# Microcontroller.net
KiCad netlist of a schematic drawn in Altium Designer
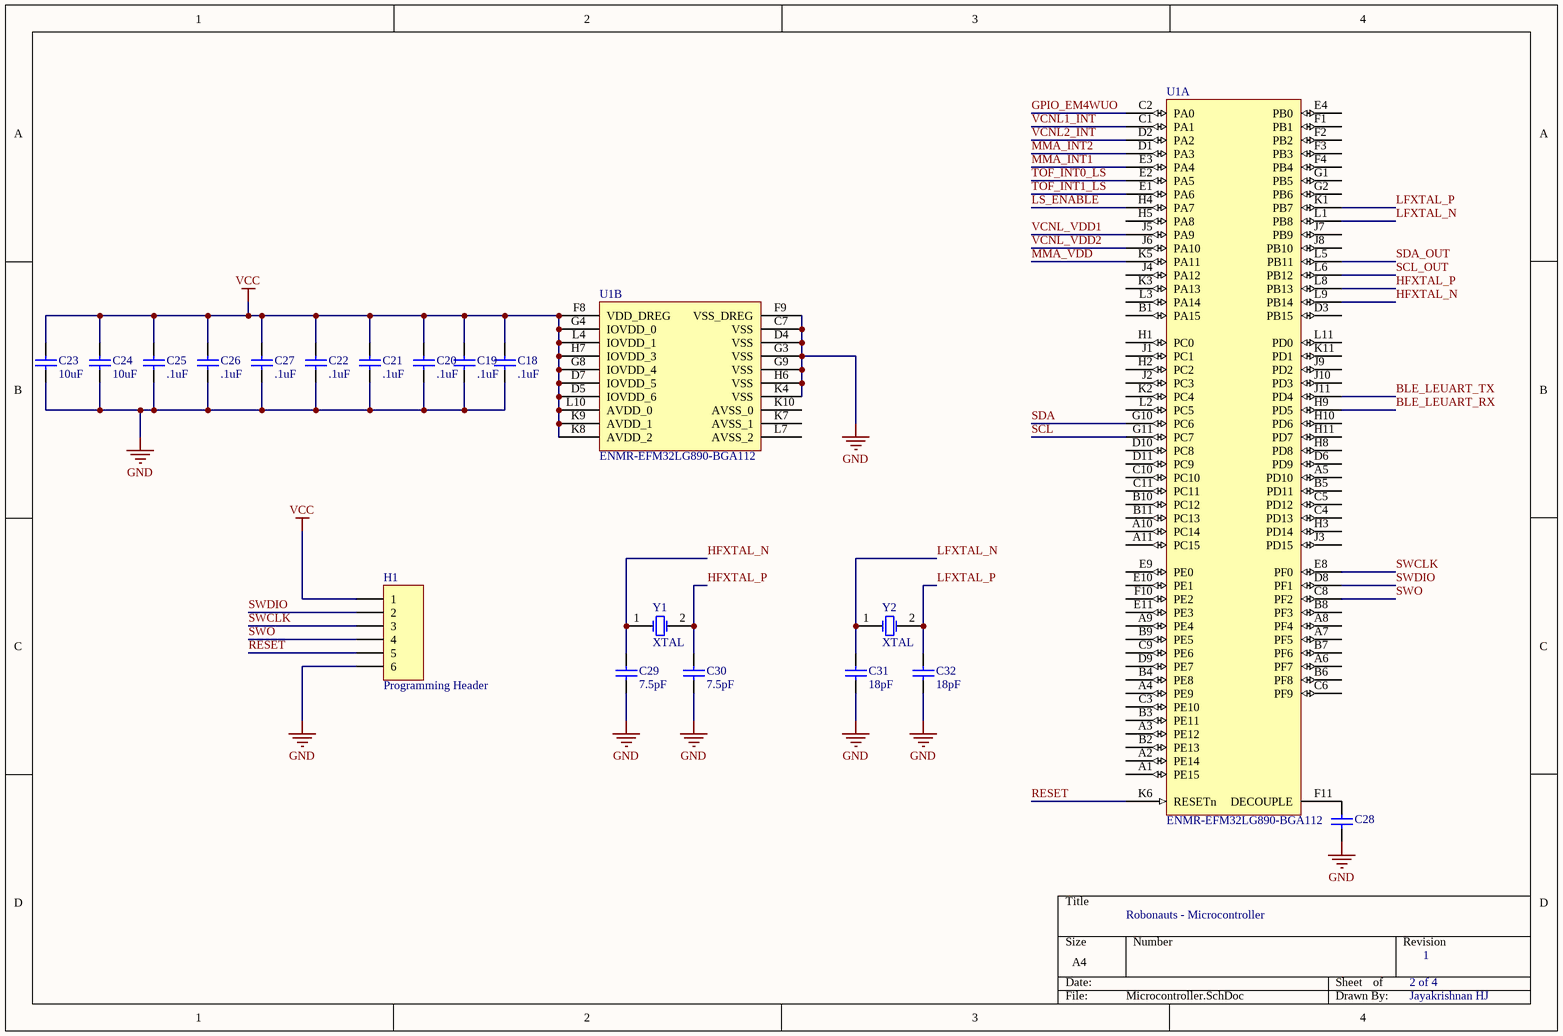
[diagram p0: Microcontroller.SchDoc]

(export (version "E")
  (design (tool "Eeschema 10.0.6"))
  (components
    (comp (ref "C18")
      (value ".1uF")
      (footprint "1608[0603]")
      (description "Capacitor (Semiconductor SIM Model)")
      (fields (field (name "Comment") "Cap Semi") (field (name "PUBLISHER") "Altium Limited"))
      (libsource (lib "Miscellaneous Devices") (part "Cap Semi"))
    )
    (comp (ref "C19")
      (value ".1uF")
      (footprint "1608[0603]")
      (description "Capacitor (Semiconductor SIM Model)")
      (fields (field (name "Comment") "Cap Semi") (field (name "PUBLISHER") "Altium Limited"))
      (libsource (lib "Miscellaneous Devices") (part "Cap Semi"))
    )
    (comp (ref "C20")
      (value ".1uF")
      (footprint "1608[0603]")
      (description "Capacitor (Semiconductor SIM Model)")
      (fields (field (name "Comment") "Cap Semi") (field (name "PUBLISHER") "Altium Limited"))
      (libsource (lib "Miscellaneous Devices") (part "Cap Semi"))
    )
    (comp (ref "C21")
      (value ".1uF")
      (footprint "1608[0603]")
      (description "Capacitor (Semiconductor SIM Model)")
      (fields (field (name "Comment") "Cap Semi") (field (name "PUBLISHER") "Altium Limited"))
      (libsource (lib "Miscellaneous Devices") (part "Cap Semi"))
    )
    (comp (ref "C22")
      (value ".1uF")
      (footprint "1608[0603]")
      (description "Capacitor (Semiconductor SIM Model)")
      (fields (field (name "Comment") "Cap Semi") (field (name "PUBLISHER") "Altium Limited"))
      (libsource (lib "Miscellaneous Devices") (part "Cap Semi"))
    )
    (comp (ref "C23")
      (value "10uF")
      (footprint "1608[0603]")
      (description "Capacitor (Semiconductor SIM Model)")
      (fields (field (name "Comment") "Cap Semi") (field (name "PUBLISHER") "Altium Limited"))
      (libsource (lib "Miscellaneous Devices") (part "Cap Semi"))
    )
    (comp (ref "C24")
      (value "10uF")
      (footprint "1608[0603]")
      (description "Capacitor (Semiconductor SIM Model)")
      (fields (field (name "Comment") "Cap Semi") (field (name "PUBLISHER") "Altium Limited"))
      (libsource (lib "Miscellaneous Devices") (part "Cap Semi"))
    )
    (comp (ref "C25")
      (value ".1uF")
      (footprint "1608[0603]")
      (description "Capacitor (Semiconductor SIM Model)")
      (fields (field (name "Comment") "Cap Semi") (field (name "PUBLISHER") "Altium Limited"))
      (libsource (lib "Miscellaneous Devices") (part "Cap Semi"))
    )
    (comp (ref "C26")
      (value ".1uF")
      (footprint "1608[0603]")
      (description "Capacitor (Semiconductor SIM Model)")
      (fields (field (name "Comment") "Cap Semi") (field (name "PUBLISHER") "Altium Limited"))
      (libsource (lib "Miscellaneous Devices") (part "Cap Semi"))
    )
    (comp (ref "C27")
      (value ".1uF")
      (footprint "1608[0603]")
      (description "Capacitor (Semiconductor SIM Model)")
      (fields (field (name "Comment") "Cap Semi") (field (name "PUBLISHER") "Altium Limited"))
      (libsource (lib "Miscellaneous Devices") (part "Cap Semi"))
    )
    (comp (ref "C28")
      (value "Cap Semi")
      (footprint "1608[0603]")
      (description "Capacitor (Semiconductor SIM Model)")
      (fields (field (name "PUBLISHER") "Altium Limited"))
      (libsource (lib "Miscellaneous Devices") (part "Cap Semi"))
    )
    (comp (ref "C29")
      (value "7.5pF")
      (footprint "C1206")
      (description "Capacitor (Semiconductor SIM Model)")
      (fields (field (name "Comment") "Cap Semi") (field (name "PUBLISHER") "Altium Limited"))
      (libsource (lib "Miscellaneous Devices") (part "Cap Semi"))
    )
    (comp (ref "C30")
      (value "7.5pF")
      (footprint "C1206")
      (description "Capacitor (Semiconductor SIM Model)")
      (fields (field (name "Comment") "Cap Semi") (field (name "PUBLISHER") "Altium Limited"))
      (libsource (lib "Miscellaneous Devices") (part "Cap Semi"))
    )
    (comp (ref "C31")
      (value "18pF")
      (footprint "C1206")
      (description "Capacitor (Semiconductor SIM Model)")
      (fields (field (name "Comment") "Cap Semi") (field (name "PUBLISHER") "Altium Limited"))
      (libsource (lib "Miscellaneous Devices") (part "Cap Semi"))
    )
    (comp (ref "C32")
      (value "18pF")
      (footprint "C1206")
      (description "Capacitor (Semiconductor SIM Model)")
      (fields (field (name "Comment") "Cap Semi") (field (name "PUBLISHER") "Altium Limited"))
      (libsource (lib "Miscellaneous Devices") (part "Cap Semi"))
    )
    (comp (ref "H1")
      (value "Programming Header")
      (footprint "HDR1X6")
      (description "Header, 6-Pin")
      (fields (field (name "PUBLISHER") "Altium Limited"))
      (libsource (lib "Miscellaneous Connectors") (part "Header 6"))
    )
    (comp (ref "U1")
      (value "ENMR-EFM32LG890-BGA112")
      (footprint "ENMR-BGA112")
      (libsource (lib "Robonauts_parts") (part "ENMR-EFM32LG890-BGA112"))
    )
    (comp (ref "Y1")
      (value "XTAL")
      (footprint "R38")
      (description "Crystal Oscillator")
      (fields (field (name "PUBLISHER") "Altium Limited"))
      (libsource (lib "Miscellaneous Devices") (part "XTAL"))
    )
    (comp (ref "Y2")
      (value "XTAL")
      (footprint "R38")
      (description "Crystal Oscillator")
      (fields (field (name "PUBLISHER") "Altium Limited"))
      (libsource (lib "Miscellaneous Devices") (part "XTAL"))
    )
  )
  (nets
    (net (code "1") (name "/BLE_LEUART_RX") (class "Default")
      (node (ref "U1") (pin "H9") (pinfunction "PD5_H9") (pintype "bidirectional"))
    )
    (net (code "2") (name "/BLE_LEUART_TX") (class "Default")
      (node (ref "U1") (pin "J11") (pinfunction "PD4_J11") (pintype "bidirectional"))
    )
    (net (code "3") (name "/GPIO_EM4WUO") (class "Default")
      (node (ref "U1") (pin "C2") (pinfunction "PA0_C2") (pintype "bidirectional"))
    )
    (net (code "4") (name "/HFXTAL_N") (class "Default")
      (node (ref "C29") (pin "2") (pinfunction "2_2") (pintype "passive"))
      (node (ref "U1") (pin "L9") (pinfunction "PB14_L9") (pintype "bidirectional"))
      (node (ref "Y1") (pin "1") (pinfunction "OSC1_1") (pintype "passive"))
    )
    (net (code "5") (name "/HFXTAL_P") (class "Default")
      (node (ref "C30") (pin "2") (pinfunction "2_2") (pintype "passive"))
      (node (ref "U1") (pin "L8") (pinfunction "PB13_L8") (pintype "bidirectional"))
      (node (ref "Y1") (pin "2") (pinfunction "OSC2_2") (pintype "passive"))
    )
    (net (code "6") (name "/LFXTAL_N") (class "Default")
      (node (ref "C31") (pin "2") (pinfunction "2_2") (pintype "passive"))
      (node (ref "U1") (pin "L1") (pinfunction "PB8_L1") (pintype "bidirectional"))
      (node (ref "Y2") (pin "1") (pinfunction "OSC1_1") (pintype "passive"))
    )
    (net (code "7") (name "/LFXTAL_P") (class "Default")
      (node (ref "C32") (pin "2") (pinfunction "2_2") (pintype "passive"))
      (node (ref "U1") (pin "K1") (pinfunction "PB7_K1") (pintype "bidirectional"))
      (node (ref "Y2") (pin "2") (pinfunction "OSC2_2") (pintype "passive"))
    )
    (net (code "8") (name "/LS_ENABLE") (class "Default")
      (node (ref "U1") (pin "H4") (pinfunction "PA7_H4") (pintype "bidirectional"))
    )
    (net (code "9") (name "/MMA_INT1") (class "Default")
      (node (ref "U1") (pin "E3") (pinfunction "PA4_E3") (pintype "bidirectional"))
    )
    (net (code "10") (name "/MMA_INT2") (class "Default")
      (node (ref "U1") (pin "D1") (pinfunction "PA3_D1") (pintype "bidirectional"))
    )
    (net (code "11") (name "/MMA_VDD") (class "Default")
      (node (ref "U1") (pin "K5") (pinfunction "PA11_K5") (pintype "bidirectional"))
    )
    (net (code "12") (name "/RESET") (class "Default")
      (node (ref "H1") (pin "5") (pinfunction "5_5") (pintype "passive"))
      (node (ref "U1") (pin "K6") (pinfunction "RESETn_K6") (pintype "input"))
    )
    (net (code "13") (name "/SCL") (class "Default")
      (node (ref "U1") (pin "G11") (pinfunction "PC7_G11") (pintype "bidirectional"))
    )
    (net (code "14") (name "/SCL_OUT") (class "Default")
      (node (ref "U1") (pin "L6") (pinfunction "PB12_L6") (pintype "bidirectional"))
    )
    (net (code "15") (name "/SDA") (class "Default")
      (node (ref "U1") (pin "G10") (pinfunction "PC6_G10") (pintype "bidirectional"))
    )
    (net (code "16") (name "/SDA_OUT") (class "Default")
      (node (ref "U1") (pin "L5") (pinfunction "PB11_L5") (pintype "bidirectional"))
    )
    (net (code "17") (name "/SWCLK") (class "Default")
      (node (ref "H1") (pin "3") (pinfunction "3_3") (pintype "passive"))
      (node (ref "U1") (pin "E8") (pinfunction "PF0_E8") (pintype "bidirectional"))
    )
    (net (code "18") (name "/SWDIO") (class "Default")
      (node (ref "H1") (pin "2") (pinfunction "2_2") (pintype "passive"))
      (node (ref "U1") (pin "D8") (pinfunction "PF1_D8") (pintype "bidirectional"))
    )
    (net (code "19") (name "/SWO") (class "Default")
      (node (ref "H1") (pin "4") (pinfunction "4_4") (pintype "passive"))
      (node (ref "U1") (pin "C8") (pinfunction "PF2_C8") (pintype "bidirectional"))
    )
    (net (code "20") (name "/TOF_INT0_LS") (class "Default")
      (node (ref "U1") (pin "E2") (pinfunction "PA5_E2") (pintype "bidirectional"))
    )
    (net (code "21") (name "/TOF_INT1_LS") (class "Default")
      (node (ref "U1") (pin "E1") (pinfunction "PA6_E1") (pintype "bidirectional"))
    )
    (net (code "22") (name "/VCNL1_INT") (class "Default")
      (node (ref "U1") (pin "C1") (pinfunction "PA1_C1") (pintype "bidirectional"))
    )
    (net (code "23") (name "/VCNL2_INT") (class "Default")
      (node (ref "U1") (pin "D2") (pinfunction "PA2_D2") (pintype "bidirectional"))
    )
    (net (code "24") (name "/VCNL_VDD1") (class "Default")
      (node (ref "U1") (pin "J5") (pinfunction "PA9_J5") (pintype "bidirectional"))
    )
    (net (code "25") (name "/VCNL_VDD2") (class "Default")
      (node (ref "U1") (pin "J6") (pinfunction "PA10_J6") (pintype "bidirectional"))
    )
    (net (code "26") (name "GND") (class "Default")
      (node (ref "C18") (pin "1") (pinfunction "1_1") (pintype "passive"))
      (node (ref "C19") (pin "1") (pinfunction "1_1") (pintype "passive"))
      (node (ref "C20") (pin "1") (pinfunction "1_1") (pintype "passive"))
      (node (ref "C21") (pin "1") (pinfunction "1_1") (pintype "passive"))
      (node (ref "C22") (pin "1") (pinfunction "1_1") (pintype "passive"))
      (node (ref "C23") (pin "1") (pinfunction "1_1") (pintype "passive"))
      (node (ref "C24") (pin "1") (pinfunction "1_1") (pintype "passive"))
      (node (ref "C25") (pin "1") (pinfunction "1_1") (pintype "passive"))
      (node (ref "C26") (pin "1") (pinfunction "1_1") (pintype "passive"))
      (node (ref "C27") (pin "1") (pinfunction "1_1") (pintype "passive"))
      (node (ref "C28") (pin "1") (pinfunction "1_1") (pintype "passive"))
      (node (ref "C29") (pin "1") (pinfunction "1_1") (pintype "passive"))
      (node (ref "C30") (pin "1") (pinfunction "1_1") (pintype "passive"))
      (node (ref "C31") (pin "1") (pinfunction "1_1") (pintype "passive"))
      (node (ref "C32") (pin "1") (pinfunction "1_1") (pintype "passive"))
      (node (ref "H1") (pin "6") (pinfunction "6_6") (pintype "passive"))
      (node (ref "U1") (pin "C7") (pinfunction "VSS_C7") (pintype "power_in"))
      (node (ref "U1") (pin "D4") (pinfunction "VSS_D4") (pintype "power_in"))
      (node (ref "U1") (pin "F9") (pinfunction "VSS_DREG_F9") (pintype "power_in"))
      (node (ref "U1") (pin "G3") (pinfunction "VSS_G3") (pintype "power_in"))
      (node (ref "U1") (pin "G9") (pinfunction "VSS_G9") (pintype "power_in"))
      (node (ref "U1") (pin "H6") (pinfunction "VSS_H6") (pintype "power_in"))
      (node (ref "U1") (pin "K4") (pinfunction "VSS_K4") (pintype "power_in"))
    )
    (net (code "27") (name "Net-(U1A-DECOUPLE)") (class "Default")
      (node (ref "C28") (pin "2") (pinfunction "2_2") (pintype "passive"))
      (node (ref "U1") (pin "F11") (pinfunction "DECOUPLE_F11") (pintype "passive"))
    )
    (net (code "28") (name "VCC") (class "Default")
      (node (ref "C18") (pin "2") (pinfunction "2_2") (pintype "passive"))
      (node (ref "C19") (pin "2") (pinfunction "2_2") (pintype "passive"))
      (node (ref "C20") (pin "2") (pinfunction "2_2") (pintype "passive"))
      (node (ref "C21") (pin "2") (pinfunction "2_2") (pintype "passive"))
      (node (ref "C22") (pin "2") (pinfunction "2_2") (pintype "passive"))
      (node (ref "C23") (pin "2") (pinfunction "2_2") (pintype "passive"))
      (node (ref "C24") (pin "2") (pinfunction "2_2") (pintype "passive"))
      (node (ref "C25") (pin "2") (pinfunction "2_2") (pintype "passive"))
      (node (ref "C26") (pin "2") (pinfunction "2_2") (pintype "passive"))
      (node (ref "C27") (pin "2") (pinfunction "2_2") (pintype "passive"))
      (node (ref "H1") (pin "1") (pinfunction "1_1") (pintype "passive"))
      (node (ref "U1") (pin "D5") (pinfunction "IOVDD_6_D5") (pintype "power_in"))
      (node (ref "U1") (pin "D7") (pinfunction "IOVDD_5_D7") (pintype "power_in"))
      (node (ref "U1") (pin "F8") (pinfunction "VDD_DREG_F8") (pintype "power_in"))
      (node (ref "U1") (pin "G4") (pinfunction "IOVDD_0_G4") (pintype "power_in"))
      (node (ref "U1") (pin "G8") (pinfunction "IOVDD_4_G8") (pintype "power_in"))
      (node (ref "U1") (pin "H7") (pinfunction "IOVDD_3_H7") (pintype "power_in"))
      (node (ref "U1") (pin "K8") (pinfunction "AVDD_2_K8") (pintype "power_in"))
      (node (ref "U1") (pin "K9") (pinfunction "AVDD_1_K9") (pintype "power_in"))
      (node (ref "U1") (pin "L10") (pinfunction "AVDD_0_L10") (pintype "power_in"))
      (node (ref "U1") (pin "L4") (pinfunction "IOVDD_1_L4") (pintype "power_in"))
    )
    (net (code "29") (name "unconnected-(U1A-PA8-PadH5)") (class "Default")
      (node (ref "U1") (pin "H5") (pinfunction "PA8_H5") (pintype "bidirectional"))
    )
    (net (code "30") (name "unconnected-(U1A-PA12-PadJ4)") (class "Default")
      (node (ref "U1") (pin "J4") (pinfunction "PA12_J4") (pintype "bidirectional"))
    )
    (net (code "31") (name "unconnected-(U1A-PA13-PadK3)") (class "Default")
      (node (ref "U1") (pin "K3") (pinfunction "PA13_K3") (pintype "bidirectional"))
    )
    (net (code "32") (name "unconnected-(U1A-PA14-PadL3)") (class "Default")
      (node (ref "U1") (pin "L3") (pinfunction "PA14_L3") (pintype "bidirectional"))
    )
    (net (code "33") (name "unconnected-(U1A-PA15-PadB1)") (class "Default")
      (node (ref "U1") (pin "B1") (pinfunction "PA15_B1") (pintype "bidirectional"))
    )
    (net (code "34") (name "unconnected-(U1A-PB0-PadE4)") (class "Default")
      (node (ref "U1") (pin "E4") (pinfunction "PB0_E4") (pintype "bidirectional"))
    )
    (net (code "35") (name "unconnected-(U1A-PB1-PadF1)") (class "Default")
      (node (ref "U1") (pin "F1") (pinfunction "PB1_F1") (pintype "bidirectional"))
    )
    (net (code "36") (name "unconnected-(U1A-PB2-PadF2)") (class "Default")
      (node (ref "U1") (pin "F2") (pinfunction "PB2_F2") (pintype "bidirectional"))
    )
    (net (code "37") (name "unconnected-(U1A-PB3-PadF3)") (class "Default")
      (node (ref "U1") (pin "F3") (pinfunction "PB3_F3") (pintype "bidirectional"))
    )
    (net (code "38") (name "unconnected-(U1A-PB4-PadF4)") (class "Default")
      (node (ref "U1") (pin "F4") (pinfunction "PB4_F4") (pintype "bidirectional"))
    )
    (net (code "39") (name "unconnected-(U1A-PB5-PadG1)") (class "Default")
      (node (ref "U1") (pin "G1") (pinfunction "PB5_G1") (pintype "bidirectional"))
    )
    (net (code "40") (name "unconnected-(U1A-PB6-PadG2)") (class "Default")
      (node (ref "U1") (pin "G2") (pinfunction "PB6_G2") (pintype "bidirectional"))
    )
    (net (code "41") (name "unconnected-(U1A-PB9-PadJ7)") (class "Default")
      (node (ref "U1") (pin "J7") (pinfunction "PB9_J7") (pintype "bidirectional"))
    )
    (net (code "42") (name "unconnected-(U1A-PB10-PadJ8)") (class "Default")
      (node (ref "U1") (pin "J8") (pinfunction "PB10_J8") (pintype "bidirectional"))
    )
    (net (code "43") (name "unconnected-(U1A-PB15-PadD3)") (class "Default")
      (node (ref "U1") (pin "D3") (pinfunction "PB15_D3") (pintype "bidirectional"))
    )
    (net (code "44") (name "unconnected-(U1A-PC0-PadH1)") (class "Default")
      (node (ref "U1") (pin "H1") (pinfunction "PC0_H1") (pintype "bidirectional"))
    )
    (net (code "45") (name "unconnected-(U1A-PC1-PadJ1)") (class "Default")
      (node (ref "U1") (pin "J1") (pinfunction "PC1_J1") (pintype "bidirectional"))
    )
    (net (code "46") (name "unconnected-(U1A-PC2-PadH2)") (class "Default")
      (node (ref "U1") (pin "H2") (pinfunction "PC2_H2") (pintype "bidirectional"))
    )
    (net (code "47") (name "unconnected-(U1A-PC3-PadJ2)") (class "Default")
      (node (ref "U1") (pin "J2") (pinfunction "PC3_J2") (pintype "bidirectional"))
    )
    (net (code "48") (name "unconnected-(U1A-PC4-PadK2)") (class "Default")
      (node (ref "U1") (pin "K2") (pinfunction "PC4_K2") (pintype "bidirectional"))
    )
    (net (code "49") (name "unconnected-(U1A-PC5-PadL2)") (class "Default")
      (node (ref "U1") (pin "L2") (pinfunction "PC5_L2") (pintype "bidirectional"))
    )
    (net (code "50") (name "unconnected-(U1A-PC8-PadD10)") (class "Default")
      (node (ref "U1") (pin "D10") (pinfunction "PC8_D10") (pintype "bidirectional"))
    )
    (net (code "51") (name "unconnected-(U1A-PC9-PadD11)") (class "Default")
      (node (ref "U1") (pin "D11") (pinfunction "PC9_D11") (pintype "bidirectional"))
    )
    (net (code "52") (name "unconnected-(U1A-PC10-PadC10)") (class "Default")
      (node (ref "U1") (pin "C10") (pinfunction "PC10_C10") (pintype "bidirectional"))
    )
    (net (code "53") (name "unconnected-(U1A-PC11-PadC11)") (class "Default")
      (node (ref "U1") (pin "C11") (pinfunction "PC11_C11") (pintype "bidirectional"))
    )
    (net (code "54") (name "unconnected-(U1A-PC12-PadB10)") (class "Default")
      (node (ref "U1") (pin "B10") (pinfunction "PC12_B10") (pintype "bidirectional"))
    )
    (net (code "55") (name "unconnected-(U1A-PC13-PadB11)") (class "Default")
      (node (ref "U1") (pin "B11") (pinfunction "PC13_B11") (pintype "bidirectional"))
    )
    (net (code "56") (name "unconnected-(U1A-PC14-PadA10)") (class "Default")
      (node (ref "U1") (pin "A10") (pinfunction "PC14_A10") (pintype "bidirectional"))
    )
    (net (code "57") (name "unconnected-(U1A-PC15-PadA11)") (class "Default")
      (node (ref "U1") (pin "A11") (pinfunction "PC15_A11") (pintype "bidirectional"))
    )
    (net (code "58") (name "unconnected-(U1A-PD0-PadL11)") (class "Default")
      (node (ref "U1") (pin "L11") (pinfunction "PD0_L11") (pintype "bidirectional"))
    )
    (net (code "59") (name "unconnected-(U1A-PD1-PadK11)") (class "Default")
      (node (ref "U1") (pin "K11") (pinfunction "PD1_K11") (pintype "bidirectional"))
    )
    (net (code "60") (name "unconnected-(U1A-PD2-PadJ9)") (class "Default")
      (node (ref "U1") (pin "J9") (pinfunction "PD2_J9") (pintype "bidirectional"))
    )
    (net (code "61") (name "unconnected-(U1A-PD3-PadJ10)") (class "Default")
      (node (ref "U1") (pin "J10") (pinfunction "PD3_J10") (pintype "bidirectional"))
    )
    (net (code "62") (name "unconnected-(U1A-PD6-PadH10)") (class "Default")
      (node (ref "U1") (pin "H10") (pinfunction "PD6_H10") (pintype "bidirectional"))
    )
    (net (code "63") (name "unconnected-(U1A-PD7-PadH11)") (class "Default")
      (node (ref "U1") (pin "H11") (pinfunction "PD7_H11") (pintype "bidirectional"))
    )
    (net (code "64") (name "unconnected-(U1A-PD8-PadH8)") (class "Default")
      (node (ref "U1") (pin "H8") (pinfunction "PD8_H8") (pintype "bidirectional"))
    )
    (net (code "65") (name "unconnected-(U1A-PD9-PadD6)") (class "Default")
      (node (ref "U1") (pin "D6") (pinfunction "PD9_D6") (pintype "bidirectional"))
    )
    (net (code "66") (name "unconnected-(U1A-PD10-PadA5)") (class "Default")
      (node (ref "U1") (pin "A5") (pinfunction "PD10_A5") (pintype "bidirectional"))
    )
    (net (code "67") (name "unconnected-(U1A-PD11-PadB5)") (class "Default")
      (node (ref "U1") (pin "B5") (pinfunction "PD11_B5") (pintype "bidirectional"))
    )
    (net (code "68") (name "unconnected-(U1A-PD12-PadC5)") (class "Default")
      (node (ref "U1") (pin "C5") (pinfunction "PD12_C5") (pintype "bidirectional"))
    )
    (net (code "69") (name "unconnected-(U1A-PD13-PadC4)") (class "Default")
      (node (ref "U1") (pin "C4") (pinfunction "PD13_C4") (pintype "bidirectional"))
    )
    (net (code "70") (name "unconnected-(U1A-PD14-PadH3)") (class "Default")
      (node (ref "U1") (pin "H3") (pinfunction "PD14_H3") (pintype "bidirectional"))
    )
    (net (code "71") (name "unconnected-(U1A-PD15-PadJ3)") (class "Default")
      (node (ref "U1") (pin "J3") (pinfunction "PD15_J3") (pintype "bidirectional"))
    )
    (net (code "72") (name "unconnected-(U1A-PE0-PadE9)") (class "Default")
      (node (ref "U1") (pin "E9") (pinfunction "PE0_E9") (pintype "bidirectional"))
    )
    (net (code "73") (name "unconnected-(U1A-PE1-PadE10)") (class "Default")
      (node (ref "U1") (pin "E10") (pinfunction "PE1_E10") (pintype "bidirectional"))
    )
    (net (code "74") (name "unconnected-(U1A-PE2-PadF10)") (class "Default")
      (node (ref "U1") (pin "F10") (pinfunction "PE2_F10") (pintype "bidirectional"))
    )
    (net (code "75") (name "unconnected-(U1A-PE3-PadE11)") (class "Default")
      (node (ref "U1") (pin "E11") (pinfunction "PE3_E11") (pintype "bidirectional"))
    )
    (net (code "76") (name "unconnected-(U1A-PE4-PadA9)") (class "Default")
      (node (ref "U1") (pin "A9") (pinfunction "PE4_A9") (pintype "bidirectional"))
    )
    (net (code "77") (name "unconnected-(U1A-PE5-PadB9)") (class "Default")
      (node (ref "U1") (pin "B9") (pinfunction "PE5_B9") (pintype "bidirectional"))
    )
    (net (code "78") (name "unconnected-(U1A-PE6-PadC9)") (class "Default")
      (node (ref "U1") (pin "C9") (pinfunction "PE6_C9") (pintype "bidirectional"))
    )
    (net (code "79") (name "unconnected-(U1A-PE7-PadD9)") (class "Default")
      (node (ref "U1") (pin "D9") (pinfunction "PE7_D9") (pintype "bidirectional"))
    )
    (net (code "80") (name "unconnected-(U1A-PE8-PadB4)") (class "Default")
      (node (ref "U1") (pin "B4") (pinfunction "PE8_B4") (pintype "bidirectional"))
    )
    (net (code "81") (name "unconnected-(U1A-PE9-PadA4)") (class "Default")
      (node (ref "U1") (pin "A4") (pinfunction "PE9_A4") (pintype "bidirectional"))
    )
    (net (code "82") (name "unconnected-(U1A-PE10-PadC3)") (class "Default")
      (node (ref "U1") (pin "C3") (pinfunction "PE10_C3") (pintype "bidirectional"))
    )
    (net (code "83") (name "unconnected-(U1A-PE11-PadB3)") (class "Default")
      (node (ref "U1") (pin "B3") (pinfunction "PE11_B3") (pintype "bidirectional"))
    )
    (net (code "84") (name "unconnected-(U1A-PE12-PadA3)") (class "Default")
      (node (ref "U1") (pin "A3") (pinfunction "PE12_A3") (pintype "bidirectional"))
    )
    (net (code "85") (name "unconnected-(U1A-PE13-PadB2)") (class "Default")
      (node (ref "U1") (pin "B2") (pinfunction "PE13_B2") (pintype "bidirectional"))
    )
    (net (code "86") (name "unconnected-(U1A-PE14-PadA2)") (class "Default")
      (node (ref "U1") (pin "A2") (pinfunction "PE14_A2") (pintype "bidirectional"))
    )
    (net (code "87") (name "unconnected-(U1A-PE15-PadA1)") (class "Default")
      (node (ref "U1") (pin "A1") (pinfunction "PE15_A1") (pintype "bidirectional"))
    )
    (net (code "88") (name "unconnected-(U1A-PF3-PadB8)") (class "Default")
      (node (ref "U1") (pin "B8") (pinfunction "PF3_B8") (pintype "bidirectional"))
    )
    (net (code "89") (name "unconnected-(U1A-PF4-PadA8)") (class "Default")
      (node (ref "U1") (pin "A8") (pinfunction "PF4_A8") (pintype "bidirectional"))
    )
    (net (code "90") (name "unconnected-(U1A-PF5-PadA7)") (class "Default")
      (node (ref "U1") (pin "A7") (pinfunction "PF5_A7") (pintype "bidirectional"))
    )
    (net (code "91") (name "unconnected-(U1A-PF6-PadB7)") (class "Default")
      (node (ref "U1") (pin "B7") (pinfunction "PF6_B7") (pintype "bidirectional"))
    )
    (net (code "92") (name "unconnected-(U1A-PF7-PadA6)") (class "Default")
      (node (ref "U1") (pin "A6") (pinfunction "PF7_A6") (pintype "bidirectional"))
    )
    (net (code "93") (name "unconnected-(U1A-PF8-PadB6)") (class "Default")
      (node (ref "U1") (pin "B6") (pinfunction "PF8_B6") (pintype "bidirectional"))
    )
    (net (code "94") (name "unconnected-(U1A-PF9-PadC6)") (class "Default")
      (node (ref "U1") (pin "C6") (pinfunction "PF9_C6") (pintype "bidirectional"))
    )
    (net (code "95") (name "unconnected-(U1B-AVSS_0-PadK10)") (class "Default")
      (node (ref "U1") (pin "K10") (pinfunction "AVSS_0_K10") (pintype "power_in"))
    )
    (net (code "96") (name "unconnected-(U1B-AVSS_1-PadK7)") (class "Default")
      (node (ref "U1") (pin "K7") (pinfunction "AVSS_1_K7") (pintype "power_in"))
    )
    (net (code "97") (name "unconnected-(U1B-AVSS_2-PadL7)") (class "Default")
      (node (ref "U1") (pin "L7") (pinfunction "AVSS_2_L7") (pintype "power_in"))
    )
  )
)
